# B101_PCIe_Socket.net
KiCad netlist of a schematic drawn in Altium Designer
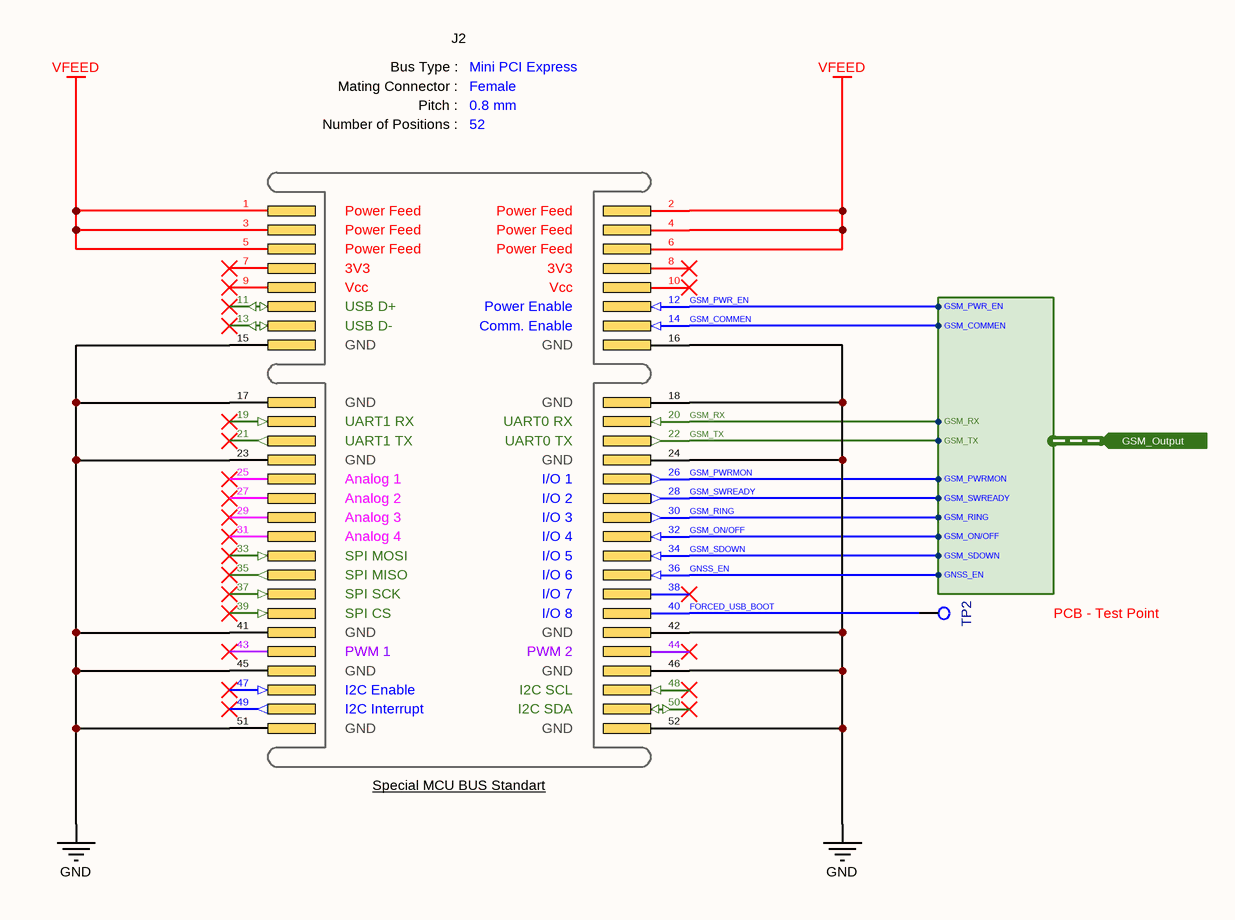
[diagram p0: B101 PCIe Socket.SchDoc]

(export (version "E")
  (design (tool "Eeschema 10.0.6"))
  (components
    (comp (ref "J2")
      (value "TE-1775862-2")
      (footprint "CONNECTOR - Mini PCIe")
      (description "Mini PCI-Express female connector.")
      (fields
        (field (name "BUS TYPE") "Mini PCI Express")
        (field (name "CONNECTOR TYPE") "Female")
        (field (name "PITCH") "0.8 mm")
        (field (name "NUMBER OF POSITIONS") "52")
      )
      (libsource (lib "P101DA_Library") (part "Connector - Mini PCI-E (Female B101)"))
    )
    (comp (ref "TP2")
      (value "PCB - Test Point")
      (footprint "Test_Point")
      (description "Test Point")
      (libsource (lib "P101DA_Library") (part "PCB - Test Point"))
    )
  )
  (nets
    (net (code "2") (name "/FORCED_USB_BOOT") (class "Default")
      (node (ref "J2") (pin "40") (pinfunction "Pin-40_40") (pintype "passive"))
      (node (ref "TP2") (pin "1") (pinfunction "1_1") (pintype "passive"))
    )
    (net (code "3") (name "/GNSS_EN") (class "Default")
      (node (ref "J2") (pin "36") (pinfunction "Pin-36_36") (pintype "input"))
    )
    (net (code "4") (name "/GSM_COMMEN") (class "Default")
      (node (ref "J2") (pin "14") (pinfunction "Pin-14_14") (pintype "input"))
    )
    (net (code "5") (name "/GSM_ON{slash}OFF") (class "Default")
      (node (ref "J2") (pin "32") (pinfunction "Pin-32_32") (pintype "input"))
    )
    (net (code "6") (name "/GSM_PWRMON") (class "Default")
      (node (ref "J2") (pin "26") (pinfunction "Pin-26_26") (pintype "output"))
    )
    (net (code "7") (name "/GSM_PWR_EN") (class "Default")
      (node (ref "J2") (pin "12") (pinfunction "Pin-12_12") (pintype "input"))
    )
    (net (code "8") (name "/GSM_RING") (class "Default")
      (node (ref "J2") (pin "30") (pinfunction "Pin-30_30") (pintype "output"))
    )
    (net (code "9") (name "/GSM_RX") (class "Default")
      (node (ref "J2") (pin "20") (pinfunction "Pin-20_20") (pintype "input"))
    )
    (net (code "10") (name "/GSM_SDOWN") (class "Default")
      (node (ref "J2") (pin "34") (pinfunction "Pin-34_34") (pintype "input"))
    )
    (net (code "11") (name "/GSM_SWREADY") (class "Default")
      (node (ref "J2") (pin "28") (pinfunction "Pin-28_28") (pintype "output"))
    )
    (net (code "12") (name "/GSM_TX") (class "Default")
      (node (ref "J2") (pin "22") (pinfunction "Pin-22_22") (pintype "output"))
    )
    (net (code "14") (name "GND") (class "Default")
      (node (ref "J2") (pin "15") (pinfunction "Pin-15_15") (pintype "power_in"))
      (node (ref "J2") (pin "16") (pinfunction "Pin-16_16") (pintype "power_in"))
      (node (ref "J2") (pin "17") (pinfunction "Pin-17_17") (pintype "power_in"))
      (node (ref "J2") (pin "18") (pinfunction "Pin-18_18") (pintype "power_in"))
      (node (ref "J2") (pin "23") (pinfunction "Pin-23_23") (pintype "power_in"))
      (node (ref "J2") (pin "24") (pinfunction "Pin-24_24") (pintype "power_in"))
      (node (ref "J2") (pin "41") (pinfunction "Pin-41_41") (pintype "power_in"))
      (node (ref "J2") (pin "42") (pinfunction "Pin-42_42") (pintype "power_in"))
      (node (ref "J2") (pin "45") (pinfunction "Pin-45_45") (pintype "power_in"))
      (node (ref "J2") (pin "46") (pinfunction "Pin-46_46") (pintype "power_in"))
      (node (ref "J2") (pin "51") (pinfunction "Pin-51_51") (pintype "power_in"))
      (node (ref "J2") (pin "52") (pinfunction "Pin-52_52") (pintype "power_in"))
    )
    (net (code "15") (name "VFEED") (class "Default")
      (node (ref "J2") (pin "1") (pinfunction "Pin-1_1") (pintype "power_in"))
      (node (ref "J2") (pin "2") (pinfunction "Pin-2_2") (pintype "power_in"))
      (node (ref "J2") (pin "3") (pinfunction "Pin-3_3") (pintype "power_in"))
      (node (ref "J2") (pin "4") (pinfunction "Pin-4_4") (pintype "power_in"))
      (node (ref "J2") (pin "5") (pinfunction "Pin-5_5") (pintype "power_in"))
      (node (ref "J2") (pin "6") (pinfunction "Pin-6_6") (pintype "power_in"))
    )
    (net (code "16") (name "unconnected-(J2-Pin-7-Pad7)") (class "Default")
      (node (ref "J2") (pin "7") (pinfunction "Pin-7_7") (pintype "power_in+no_connect"))
    )
    (net (code "17") (name "unconnected-(J2-Pin-8-Pad8)") (class "Default")
      (node (ref "J2") (pin "8") (pinfunction "Pin-8_8") (pintype "power_in+no_connect"))
    )
    (net (code "18") (name "unconnected-(J2-Pin-9-Pad9)") (class "Default")
      (node (ref "J2") (pin "9") (pinfunction "Pin-9_9") (pintype "power_in+no_connect"))
    )
    (net (code "19") (name "unconnected-(J2-Pin-10-Pad10)") (class "Default")
      (node (ref "J2") (pin "10") (pinfunction "Pin-10_10") (pintype "power_in+no_connect"))
    )
    (net (code "20") (name "unconnected-(J2-Pin-11-Pad11)") (class "Default")
      (node (ref "J2") (pin "11") (pinfunction "Pin-11_11") (pintype "bidirectional+no_connect"))
    )
    (net (code "21") (name "unconnected-(J2-Pin-13-Pad13)") (class "Default")
      (node (ref "J2") (pin "13") (pinfunction "Pin-13_13") (pintype "bidirectional+no_connect"))
    )
    (net (code "22") (name "unconnected-(J2-Pin-19-Pad19)") (class "Default")
      (node (ref "J2") (pin "19") (pinfunction "Pin-19_19") (pintype "input+no_connect"))
    )
    (net (code "23") (name "unconnected-(J2-Pin-21-Pad21)") (class "Default")
      (node (ref "J2") (pin "21") (pinfunction "Pin-21_21") (pintype "output+no_connect"))
    )
    (net (code "24") (name "unconnected-(J2-Pin-25-Pad25)") (class "Default")
      (node (ref "J2") (pin "25") (pinfunction "Pin-25_25") (pintype "passive+no_connect"))
    )
    (net (code "25") (name "unconnected-(J2-Pin-27-Pad27)") (class "Default")
      (node (ref "J2") (pin "27") (pinfunction "Pin-27_27") (pintype "passive+no_connect"))
    )
    (net (code "26") (name "unconnected-(J2-Pin-29-Pad29)") (class "Default")
      (node (ref "J2") (pin "29") (pinfunction "Pin-29_29") (pintype "passive+no_connect"))
    )
    (net (code "27") (name "unconnected-(J2-Pin-31-Pad31)") (class "Default")
      (node (ref "J2") (pin "31") (pinfunction "Pin-31_31") (pintype "passive+no_connect"))
    )
    (net (code "28") (name "unconnected-(J2-Pin-33-Pad33)") (class "Default")
      (node (ref "J2") (pin "33") (pinfunction "Pin-33_33") (pintype "input+no_connect"))
    )
    (net (code "29") (name "unconnected-(J2-Pin-35-Pad35)") (class "Default")
      (node (ref "J2") (pin "35") (pinfunction "Pin-35_35") (pintype "output+no_connect"))
    )
    (net (code "30") (name "unconnected-(J2-Pin-37-Pad37)") (class "Default")
      (node (ref "J2") (pin "37") (pinfunction "Pin-37_37") (pintype "input+no_connect"))
    )
    (net (code "31") (name "unconnected-(J2-Pin-38-Pad38)") (class "Default")
      (node (ref "J2") (pin "38") (pinfunction "Pin-38_38") (pintype "passive+no_connect"))
    )
    (net (code "32") (name "unconnected-(J2-Pin-39-Pad39)") (class "Default")
      (node (ref "J2") (pin "39") (pinfunction "Pin-39_39") (pintype "input+no_connect"))
    )
    (net (code "33") (name "unconnected-(J2-Pin-43-Pad43)") (class "Default")
      (node (ref "J2") (pin "43") (pinfunction "Pin-43_43") (pintype "passive+no_connect"))
    )
    (net (code "34") (name "unconnected-(J2-Pin-44-Pad44)") (class "Default")
      (node (ref "J2") (pin "44") (pinfunction "Pin-44_44") (pintype "passive+no_connect"))
    )
    (net (code "35") (name "unconnected-(J2-Pin-47-Pad47)") (class "Default")
      (node (ref "J2") (pin "47") (pinfunction "Pin-47_47") (pintype "input+no_connect"))
    )
    (net (code "36") (name "unconnected-(J2-Pin-48-Pad48)") (class "Default")
      (node (ref "J2") (pin "48") (pinfunction "Pin-48_48") (pintype "input+no_connect"))
    )
    (net (code "37") (name "unconnected-(J2-Pin-49-Pad49)") (class "Default")
      (node (ref "J2") (pin "49") (pinfunction "Pin-49_49") (pintype "output+no_connect"))
    )
    (net (code "38") (name "unconnected-(J2-Pin-50-Pad50)") (class "Default")
      (node (ref "J2") (pin "50") (pinfunction "Pin-50_50") (pintype "bidirectional+no_connect"))
    )
  )
)
